# circuito_tesi.net
KiCad netlist of a schematic drawn in EAGLE
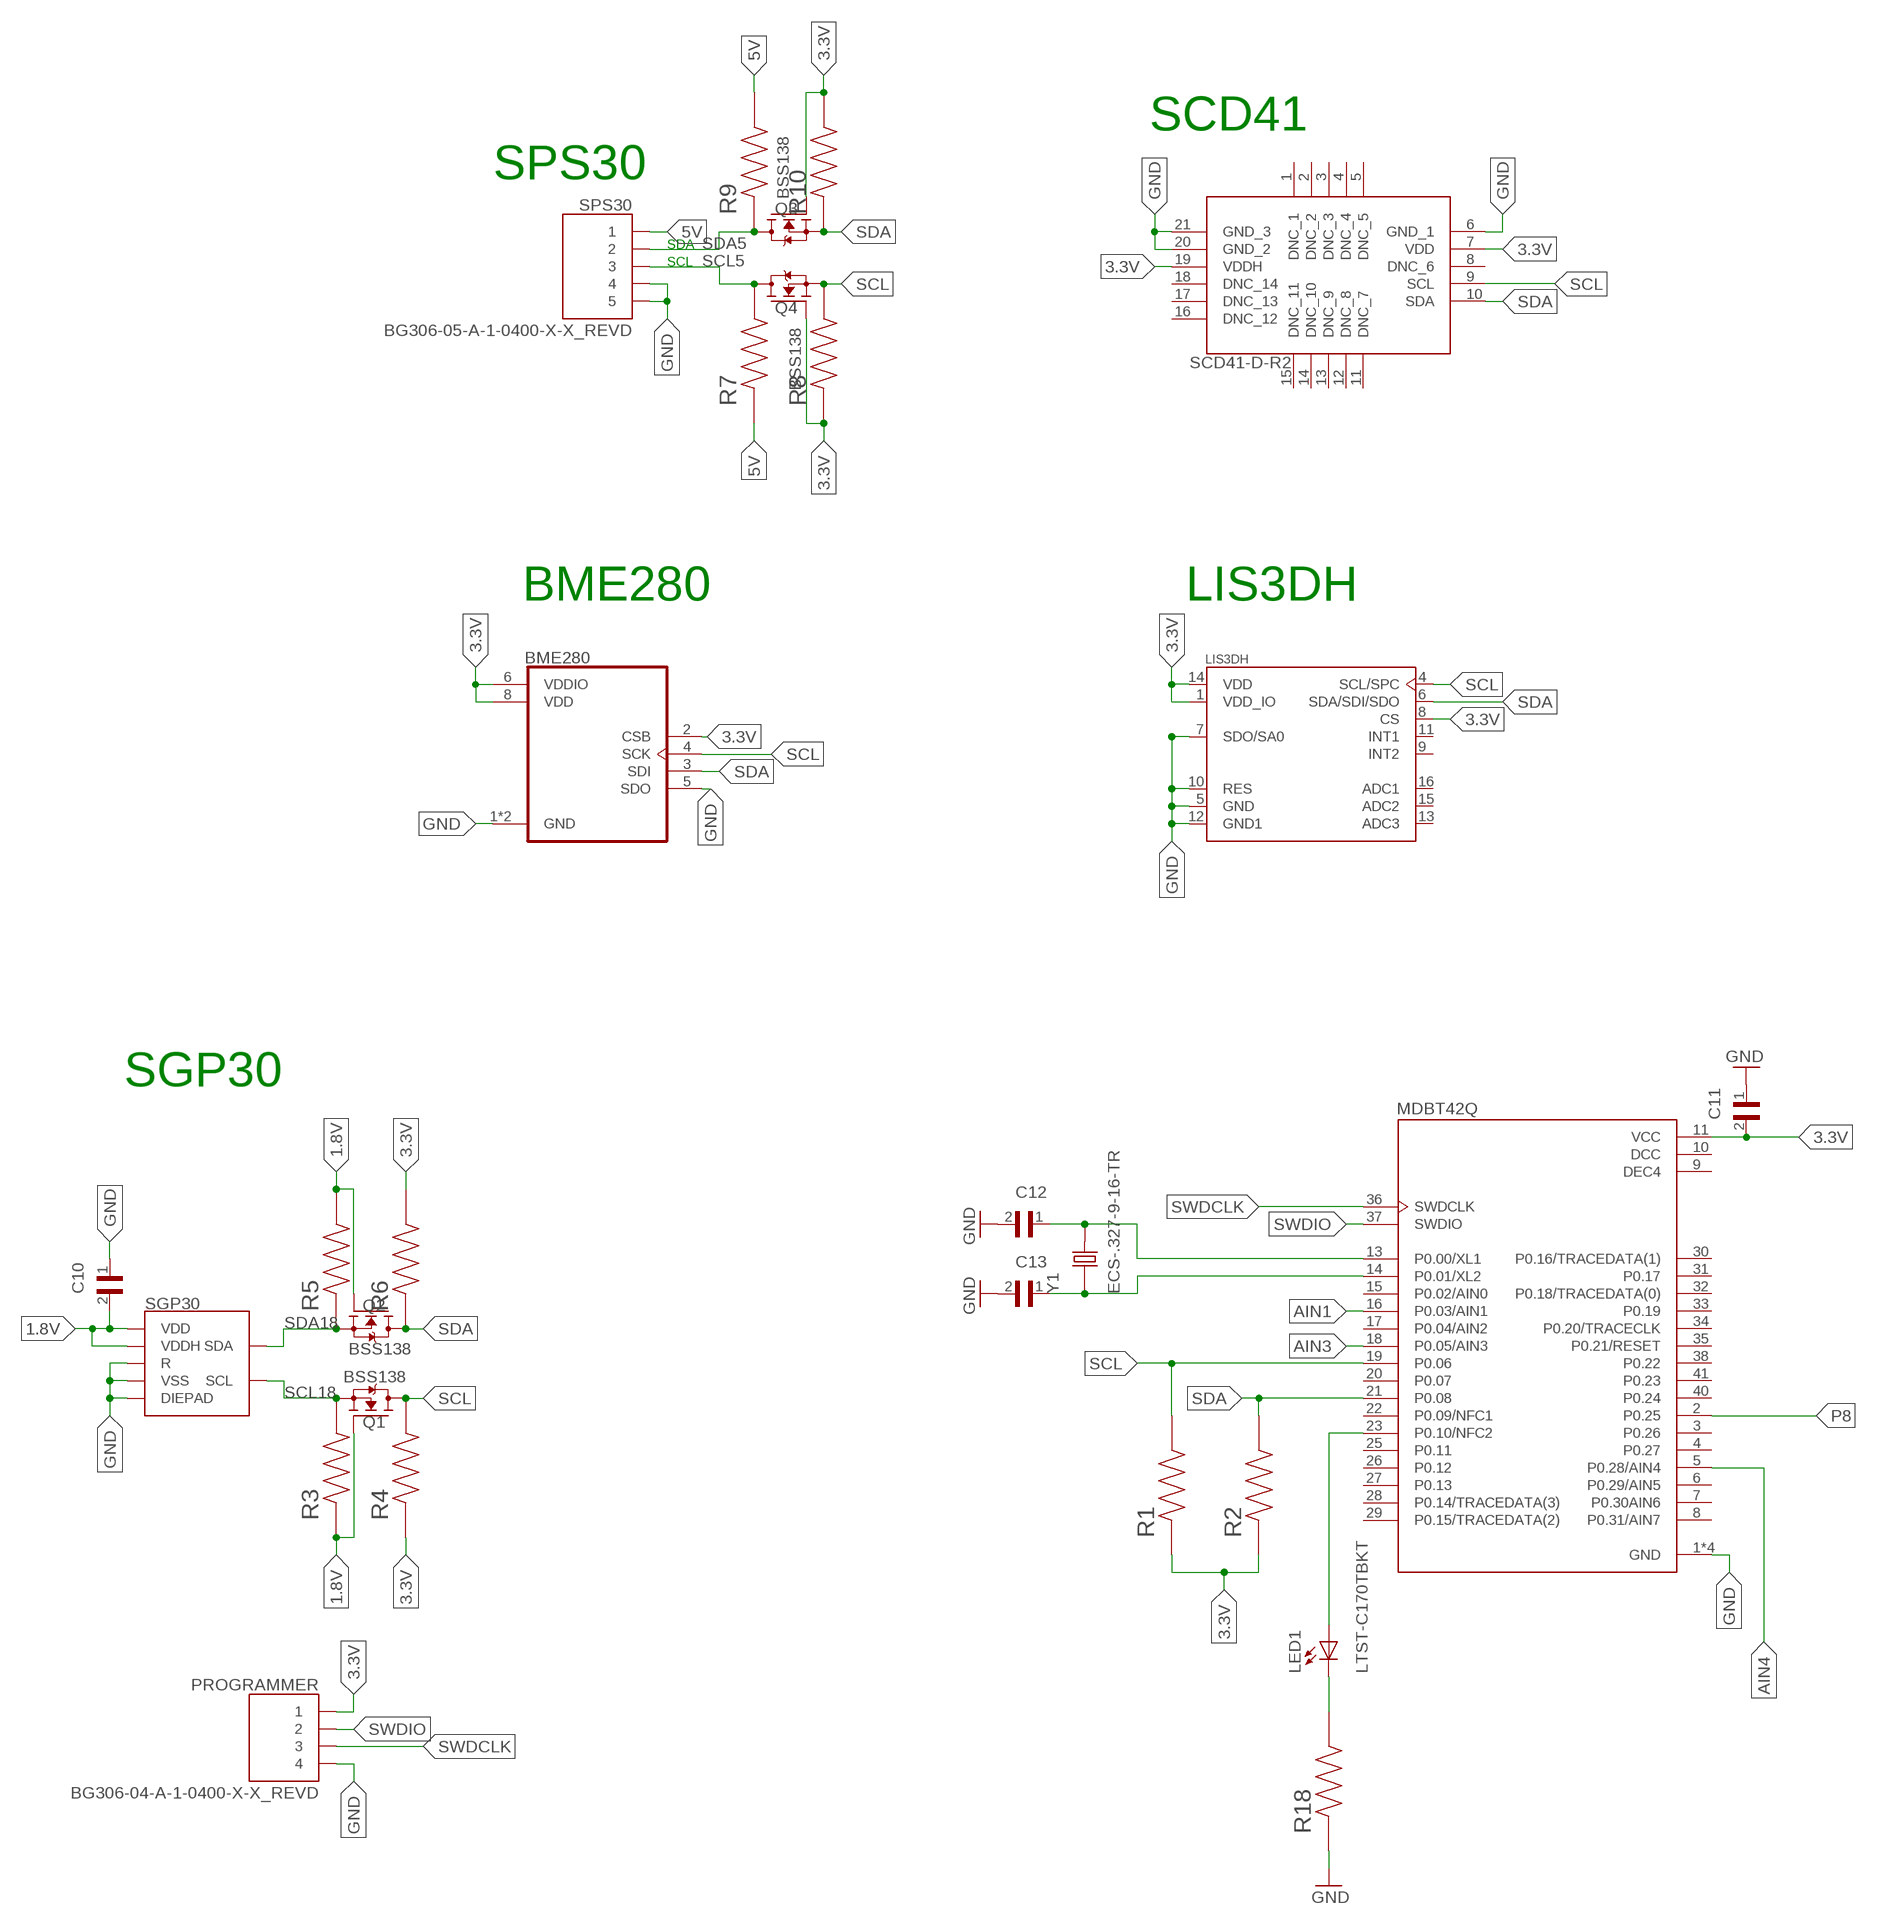
[diagram p0: schematic, sheet 1, part 1 of 2]
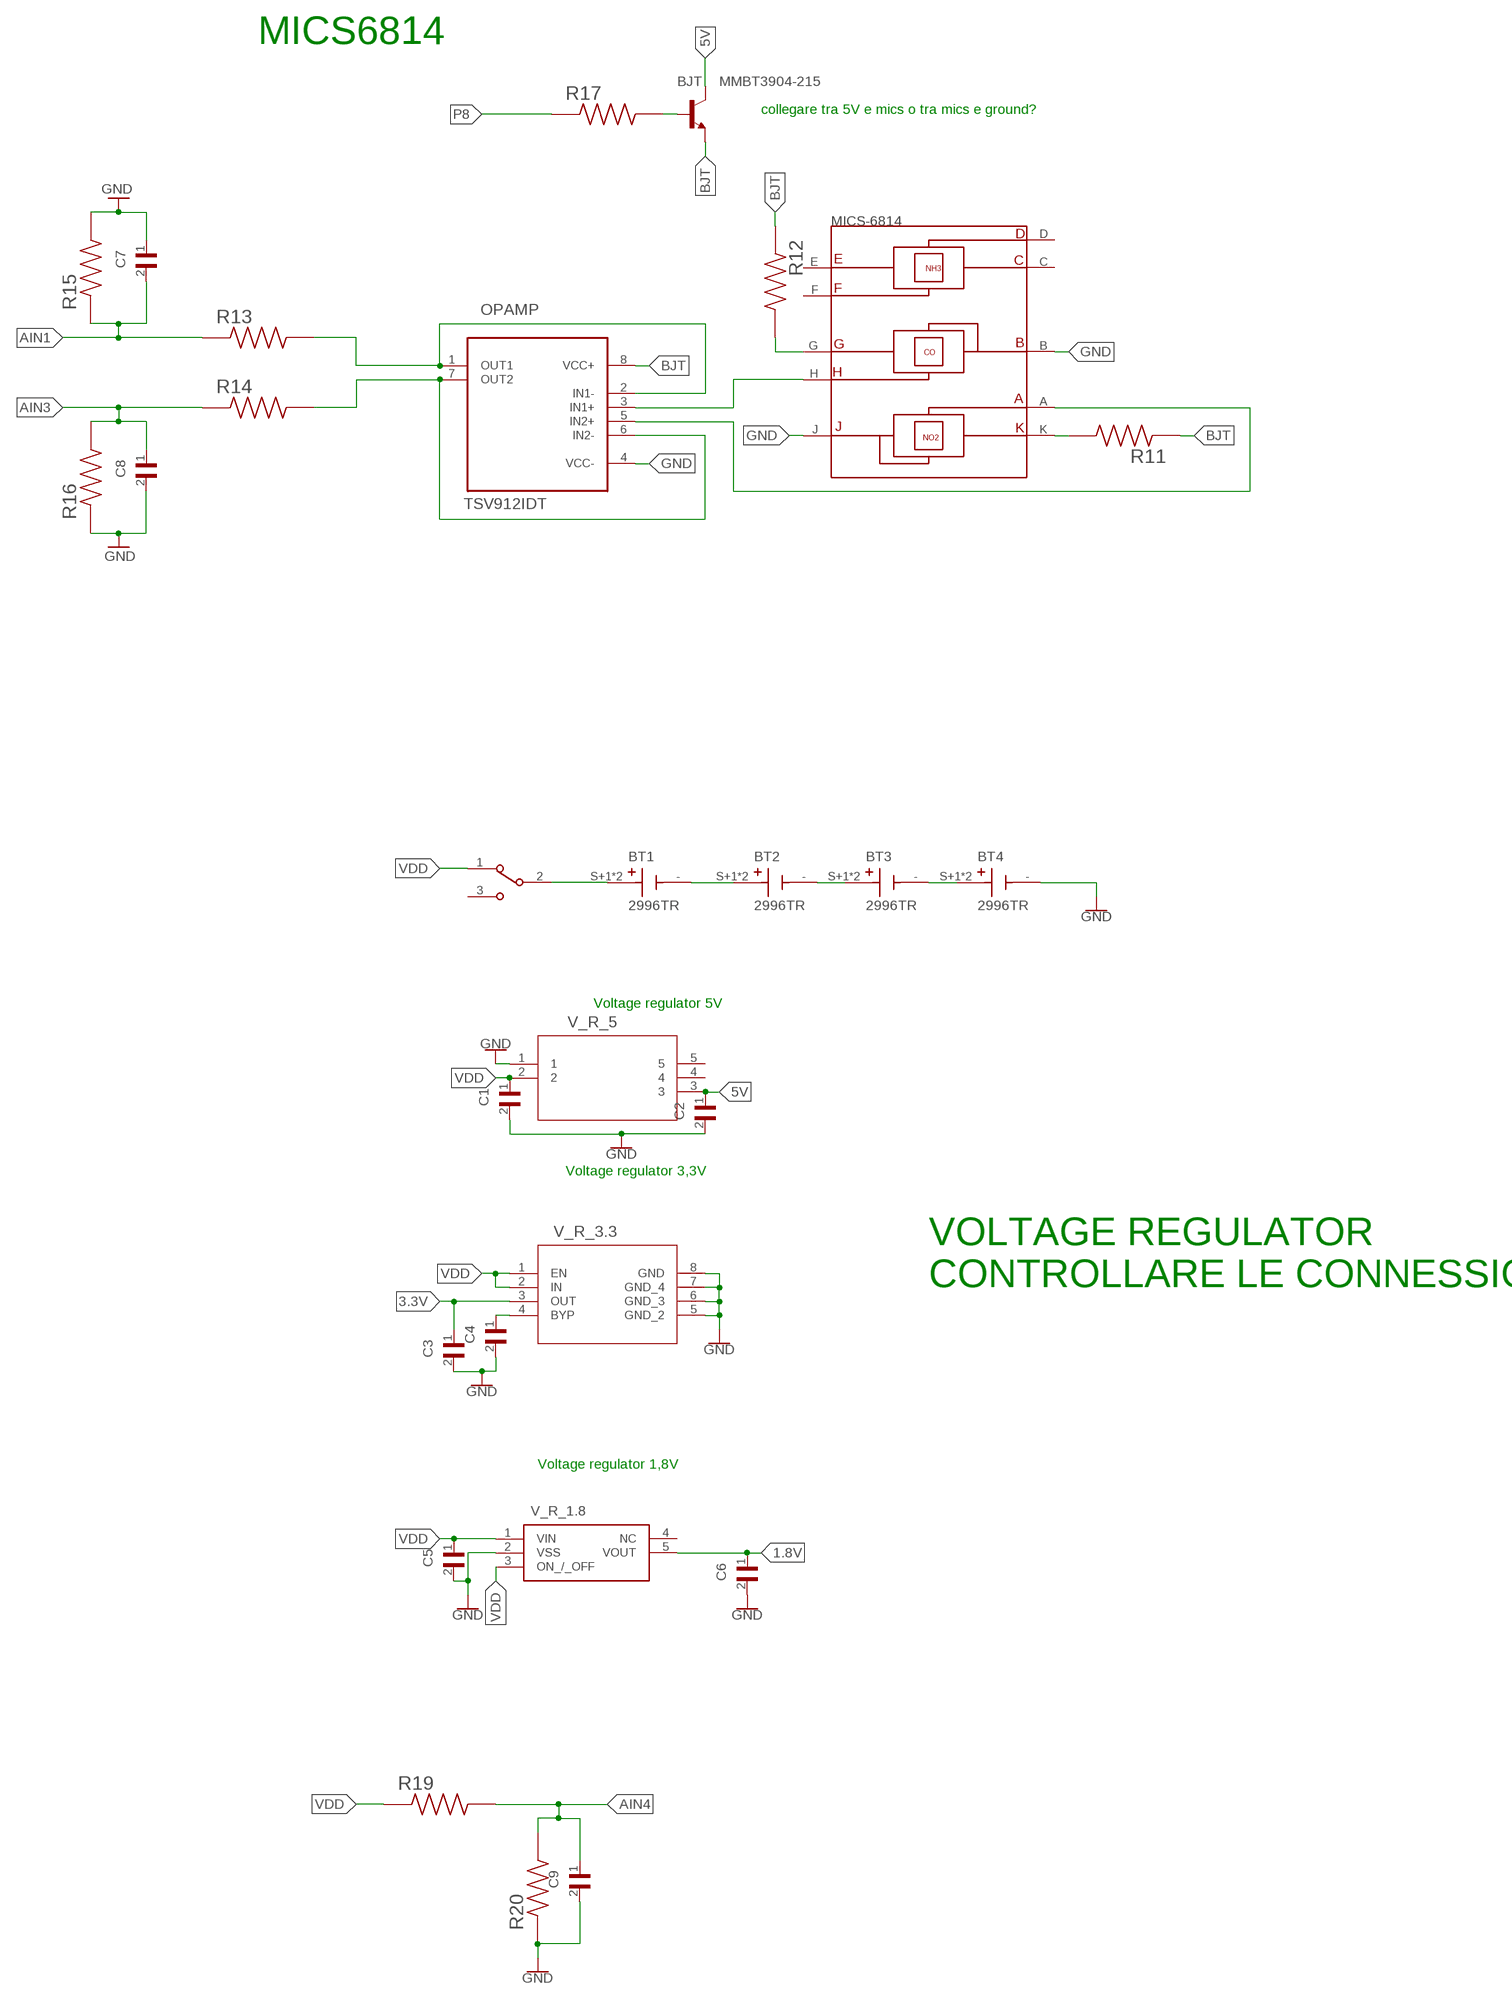
[diagram p1: schematic, sheet 1, part 2 of 2]

(export (version "E")
  (design (tool "Eeschema 10.0.6"))
  (components
    (comp (ref "BJT")
      (value "MMBT3904-215")
      (footprint "eagle-import:SOT95P230X110-3N")
      (fields
        (field (name "DIGI-KEY_PART_NUMBER") "1727-4044-2-ND")
        (field (name "MF") "Nexperia USA")
        (field (name "MP") "MMBT3904,215")
      )
      (libsource (lib "eagle-import") (part "MMBT3904-215"))
    )
    (comp (ref "BT1")
      (value "2996TR")
      (footprint "eagle-import:BAT_2996TR")
      (fields (field (name "DIGI-KEY_PART_NUMBER") "36-2996TR-ND") (field (name "MF") "Keystone Electronics"))
      (libsource (lib "eagle-import") (part "2996TR"))
    )
    (comp (ref "BT2")
      (value "2996TR")
      (footprint "eagle-import:BAT_2996TR")
      (fields (field (name "DIGI-KEY_PART_NUMBER") "36-2996TR-ND") (field (name "MF") "Keystone Electronics"))
      (libsource (lib "eagle-import") (part "2996TR"))
    )
    (comp (ref "BT3")
      (value "2996TR")
      (footprint "eagle-import:BAT_2996TR")
      (fields (field (name "DIGI-KEY_PART_NUMBER") "36-2996TR-ND") (field (name "MF") "Keystone Electronics"))
      (libsource (lib "eagle-import") (part "2996TR"))
    )
    (comp (ref "BT4")
      (value "2996TR")
      (footprint "eagle-import:BAT_2996TR")
      (fields (field (name "DIGI-KEY_PART_NUMBER") "36-2996TR-ND") (field (name "MF") "Keystone Electronics"))
      (libsource (lib "eagle-import") (part "2996TR"))
    )
    (comp (ref "C1")
      (value "C0402H102J5GACTU")
      (footprint "eagle-import:CAPC1005X55N")
      (fields (field (name "MF") "KEMET"))
      (libsource (lib "eagle-import") (part "C0402H102J5GACTU"))
    )
    (comp (ref "C2")
      (value "C0402H102J5GACTU")
      (footprint "eagle-import:CAPC1005X55N")
      (fields (field (name "MF") "KEMET"))
      (libsource (lib "eagle-import") (part "C0402H102J5GACTU"))
    )
    (comp (ref "C3")
      (value "C0402H102J5GACTU")
      (footprint "eagle-import:CAPC1005X55N")
      (fields (field (name "MF") "KEMET"))
      (libsource (lib "eagle-import") (part "C0402H102J5GACTU"))
    )
    (comp (ref "C4")
      (value "C0402H102J5GACTU")
      (footprint "eagle-import:CAPC1005X55N")
      (fields (field (name "MF") "KEMET"))
      (libsource (lib "eagle-import") (part "C0402H102J5GACTU"))
    )
    (comp (ref "C5")
      (value "C0402H102J5GACTU")
      (footprint "eagle-import:CAPC1005X55N")
      (fields (field (name "MF") "KEMET"))
      (libsource (lib "eagle-import") (part "C0402H102J5GACTU"))
    )
    (comp (ref "C6")
      (value "C0402H102J5GACTU")
      (footprint "eagle-import:CAPC1005X55N")
      (fields (field (name "MF") "KEMET"))
      (libsource (lib "eagle-import") (part "C0402H102J5GACTU"))
    )
    (comp (ref "C7")
      (value "C0402H102J5GACTU")
      (footprint "eagle-import:CAPC1005X55N")
      (fields (field (name "MF") "KEMET"))
      (libsource (lib "eagle-import") (part "C0402H102J5GACTU"))
    )
    (comp (ref "C8")
      (value "C0402H102J5GACTU")
      (footprint "eagle-import:CAPC1005X55N")
      (fields (field (name "MF") "KEMET"))
      (libsource (lib "eagle-import") (part "C0402H102J5GACTU"))
    )
    (comp (ref "C9")
      (value "C0402H102J5GACTU")
      (footprint "eagle-import:CAPC1005X55N")
      (fields (field (name "MF") "KEMET"))
      (libsource (lib "eagle-import") (part "C0402H102J5GACTU"))
    )
    (comp (ref "C10")
      (value "C0402H102J5GACTU")
      (footprint "eagle-import:CAPC1005X55N")
      (fields (field (name "MF") "KEMET"))
      (libsource (lib "eagle-import") (part "C0402H102J5GACTU"))
    )
    (comp (ref "C11")
      (value "C0402H102J5GACTU")
      (footprint "eagle-import:CAPC1005X55N")
      (fields (field (name "MF") "KEMET"))
      (libsource (lib "eagle-import") (part "C0402H102J5GACTU"))
    )
    (comp (ref "C12")
      (value "C0402H102J5GACTU")
      (footprint "eagle-import:CAPC1005X55N")
      (fields (field (name "MF") "KEMET"))
      (libsource (lib "eagle-import") (part "C0402H102J5GACTU"))
    )
    (comp (ref "C13")
      (value "C0402H102J5GACTU")
      (footprint "eagle-import:CAPC1005X55N")
      (fields (field (name "MF") "KEMET"))
      (libsource (lib "eagle-import") (part "C0402H102J5GACTU"))
    )
    (comp (ref "IC1")
      (value "SCD41-D-R2")
      (footprint "eagle-import:SCD41DR2")
      (fields (field (name "MOUSER_PART_NUMBER") "403-SCD41-D-R2"))
      (libsource (lib "eagle-import") (part "SCD41-D-R2"))
    )
    (comp (ref "LED1")
      (value "LTST-C170TBKT")
      (footprint "eagle-import:DIOC200X125X110")
      (fields (field (name "MF") "Lite-On Electronics"))
      (libsource (lib "eagle-import") (part "LTST-C170TBKT"))
    )
    (comp (ref "MDBT42Q")
      (value "317030213")
      (footprint "eagle-import:XCVR_317030213")
      (fields (field (name "DIGI-KEY_PART_NUMBER") "1597-1434-ND") (field (name "MF") "Seeed Technology"))
      (libsource (lib "eagle-import") (part "317030213"))
    )
    (comp (ref "OPAMP")
      (value "TSV912IDT")
      (footprint "eagle-import:SOIC127P600X175-8N")
      (fields (field (name "MF") "STMicroelectronics"))
      (libsource (lib "eagle-import") (part "TSV912IDT"))
    )
    (comp (ref "PROGRAMMER")
      (value "BG306-04-A-1-0400-X-X_REVD")
      (footprint "eagle-import:GCT_BG306-04-A-1-0400-X-X_REVD")
      (fields
        (field (name "DIGI-KEY_PART_NUMBER") "2073-BG306-04-A-1-0400-L-BTR-ND")
        (field (name "MF") "Global Connector Technology")
        (field (name "MP") "BG306-04-A-1-0400-L-B")
      )
      (libsource (lib "eagle-import") (part "BG306-04-A-1-0400-X-X_REVD"))
    )
    (comp (ref "Q1")
      (value "BSS138")
      (footprint "eagle-import:SOT95P240X111-3N")
      (fields (field (name "DIGI-KEY_PART_NUMBER") "BSS138TR-ND") (field (name "MF") "ON Semiconductor"))
      (libsource (lib "eagle-import") (part "BSS138"))
    )
    (comp (ref "Q2")
      (value "BSS138")
      (footprint "eagle-import:SOT95P240X111-3N")
      (fields (field (name "DIGI-KEY_PART_NUMBER") "BSS138TR-ND") (field (name "MF") "ON Semiconductor"))
      (libsource (lib "eagle-import") (part "BSS138"))
    )
    (comp (ref "Q3")
      (value "BSS138")
      (footprint "eagle-import:SOT95P240X111-3N")
      (fields (field (name "DIGI-KEY_PART_NUMBER") "BSS138TR-ND") (field (name "MF") "ON Semiconductor"))
      (libsource (lib "eagle-import") (part "BSS138"))
    )
    (comp (ref "Q4")
      (value "BSS138")
      (footprint "eagle-import:SOT95P240X111-3N")
      (fields (field (name "DIGI-KEY_PART_NUMBER") "BSS138TR-ND") (field (name "MF") "ON Semiconductor"))
      (libsource (lib "eagle-import") (part "BSS138"))
    )
    (comp (ref "R1")
      (value "8-1879333-9")
      (footprint "eagle-import:RESC1005X35N")
      (fields (field (name "MF") "TE Connectivity"))
      (libsource (lib "eagle-import") (part "8-1879333-9"))
    )
    (comp (ref "R2")
      (value "8-1879333-9")
      (footprint "eagle-import:RESC1005X35N")
      (fields (field (name "MF") "TE Connectivity"))
      (libsource (lib "eagle-import") (part "8-1879333-9"))
    )
    (comp (ref "R3")
      (value "8-1879333-9")
      (footprint "eagle-import:RESC1005X35N")
      (fields (field (name "MF") "TE Connectivity"))
      (libsource (lib "eagle-import") (part "8-1879333-9"))
    )
    (comp (ref "R4")
      (value "8-1879333-9")
      (footprint "eagle-import:RESC1005X35N")
      (fields (field (name "MF") "TE Connectivity"))
      (libsource (lib "eagle-import") (part "8-1879333-9"))
    )
    (comp (ref "R5")
      (value "8-1879333-9")
      (footprint "eagle-import:RESC1005X35N")
      (fields (field (name "MF") "TE Connectivity"))
      (libsource (lib "eagle-import") (part "8-1879333-9"))
    )
    (comp (ref "R6")
      (value "8-1879333-9")
      (footprint "eagle-import:RESC1005X35N")
      (fields (field (name "MF") "TE Connectivity"))
      (libsource (lib "eagle-import") (part "8-1879333-9"))
    )
    (comp (ref "R7")
      (value "8-1879333-9")
      (footprint "eagle-import:RESC1005X35N")
      (fields (field (name "MF") "TE Connectivity"))
      (libsource (lib "eagle-import") (part "8-1879333-9"))
    )
    (comp (ref "R8")
      (value "8-1879333-9")
      (footprint "eagle-import:RESC1005X35N")
      (fields (field (name "MF") "TE Connectivity"))
      (libsource (lib "eagle-import") (part "8-1879333-9"))
    )
    (comp (ref "R9")
      (value "8-1879333-9")
      (footprint "eagle-import:RESC1005X35N")
      (fields (field (name "MF") "TE Connectivity"))
      (libsource (lib "eagle-import") (part "8-1879333-9"))
    )
    (comp (ref "R10")
      (value "8-1879333-9")
      (footprint "eagle-import:RESC1005X35N")
      (fields (field (name "MF") "TE Connectivity"))
      (libsource (lib "eagle-import") (part "8-1879333-9"))
    )
    (comp (ref "R11")
      (value "8-1879333-9")
      (footprint "eagle-import:RESC1005X35N")
      (fields (field (name "MF") "TE Connectivity"))
      (libsource (lib "eagle-import") (part "8-1879333-9"))
    )
    (comp (ref "R12")
      (value "8-1879333-9")
      (footprint "eagle-import:RESC1005X35N")
      (fields (field (name "MF") "TE Connectivity"))
      (libsource (lib "eagle-import") (part "8-1879333-9"))
    )
    (comp (ref "R13")
      (value "8-1879333-9")
      (footprint "eagle-import:RESC1005X35N")
      (fields (field (name "MF") "TE Connectivity"))
      (libsource (lib "eagle-import") (part "8-1879333-9"))
    )
    (comp (ref "R14")
      (value "8-1879333-9")
      (footprint "eagle-import:RESC1005X35N")
      (fields (field (name "MF") "TE Connectivity"))
      (libsource (lib "eagle-import") (part "8-1879333-9"))
    )
    (comp (ref "R15")
      (value "8-1879333-9")
      (footprint "eagle-import:RESC1005X35N")
      (fields (field (name "MF") "TE Connectivity"))
      (libsource (lib "eagle-import") (part "8-1879333-9"))
    )
    (comp (ref "R16")
      (value "8-1879333-9")
      (footprint "eagle-import:RESC1005X35N")
      (fields (field (name "MF") "TE Connectivity"))
      (libsource (lib "eagle-import") (part "8-1879333-9"))
    )
    (comp (ref "R17")
      (value "8-1879333-9")
      (footprint "eagle-import:RESC1005X35N")
      (fields (field (name "MF") "TE Connectivity"))
      (libsource (lib "eagle-import") (part "8-1879333-9"))
    )
    (comp (ref "R18")
      (value "8-1879333-9")
      (footprint "eagle-import:RESC1005X35N")
      (fields (field (name "MF") "TE Connectivity"))
      (libsource (lib "eagle-import") (part "8-1879333-9"))
    )
    (comp (ref "R19")
      (value "8-1879333-9")
      (footprint "eagle-import:RESC1005X35N")
      (fields (field (name "MF") "TE Connectivity"))
      (libsource (lib "eagle-import") (part "8-1879333-9"))
    )
    (comp (ref "R20")
      (value "8-1879333-9")
      (footprint "eagle-import:RESC1005X35N")
      (fields (field (name "MF") "TE Connectivity"))
      (libsource (lib "eagle-import") (part "8-1879333-9"))
    )
    (comp (ref "S1")
      (value "EG1213")
      (footprint "eagle-import:SW_EG1213")
      (fields (field (name "DIGI-KEY_PART_NUMBER") "EG1906-ND") (field (name "MF") "E-Switch"))
      (libsource (lib "eagle-import") (part "EG1213"))
    )
    (comp (ref "SGP30")
      (value "SGP30")
      (footprint "eagle-import:SGP30")
      (fields (field (name "MF") "Sensirion AG"))
      (libsource (lib "eagle-import") (part "SGP30"))
    )
    (comp (ref "SPS30")
      (value "BG306-05-A-1-0400-X-X_REVD")
      (footprint "eagle-import:GCT_BG306-05-A-1-0400-X-X_REVD")
      (fields
        (field (name "DIGI-KEY_PART_NUMBER") "2073-BG306-05-A-1-0400-L-BTR-ND")
        (field (name "MF") "Global Connector Technology")
        (field (name "MP") "BG306-05-A-1-0400-L-B")
      )
      (libsource (lib "eagle-import") (part "BG306-05-A-1-0400-X-X_REVD"))
    )
    (comp (ref "U3")
      (value "MICS-6814")
      (footprint "eagle-import:SENSOR_MICS-6814")
      (fields (field (name "MF") "MikroElektronika"))
      (libsource (lib "eagle-import") (part "MICS-6814"))
    )
    (comp (ref "U6")
      (value "BME280")
      (footprint "eagle-import:PSON65P250X250X100-8N")
      (fields (field (name "MF") "Bosch"))
      (libsource (lib "eagle-import") (part "BME280"))
    )
    (comp (ref "U7")
      (value "LIS3DH")
      (footprint "eagle-import:PQFN50P300X300X100-16N")
      (fields (field (name "DIGI-KEY_PART_NUMBER") "497-10610-ND") (field (name "MF") "STMicroelectronics"))
      (libsource (lib "eagle-import") (part "LIS3DH"))
    )
    (comp (ref "V_R_1.8")
      (value "S-1318D18-M5T1U4")
      (footprint "eagle-import:SOT95P275X130-5N")
      (fields (field (name "MOUSER_PART_NUMBER") "628-S-1318D18-M5T1U4"))
      (libsource (lib "eagle-import") (part "S-1318D18-M5T1U4"))
    )
    (comp (ref "V_R_3.3")
      (value "MIC5219-3.3YMMMSOP-8LD-PL-1_MCH")
      (footprint "eagle-import:MSOP-8LD-PL-1_MCH")
      (fields
        (field (name "MANUFACTURER_PART_NUMBER") "MIC5219-3.3YMM")
        (field (name "COPYRIGHT") "Copyright (C) 2022 Ultra Librarian. All rights reserved.")
      )
      (libsource (lib "eagle-import") (part "MIC5219-3.3YMMMSOP-8LD-PL-1_MCH"))
    )
    (comp (ref "V_R_5")
      (value "MC78LC50NTRGTSOT23-5_ONS")
      (footprint "eagle-import:TSOT23-5_ONS")
      (fields
        (field (name "MANUFACTURER_PART_NUMBER") "MC78LC50NTRG")
        (field (name "COPYRIGHT") "Copyright (C) 2022 Ultra Librarian. All rights reserved.")
      )
      (libsource (lib "eagle-import") (part "MC78LC50NTRGTSOT23-5_ONS"))
    )
    (comp (ref "Y1")
      (value "ECS-.327-9-16-TR")
      (footprint "eagle-import:XTAL_ECS-.327-9-16-TR")
      (fields (field (name "DIGI-KEY_PART_NUMBER") "XC2132TR-ND") (field (name "MF") "ECS Inc."))
      (libsource (lib "eagle-import") (part "ECS-.327-9-16-TR"))
    )
  )
  (nets
    (net (code "1") (name "/DCC") (class "Default")
      (node (ref "MDBT42Q") (pin "10") (pinfunction "DCC_10") (pintype "power_in"))
    )
    (net (code "2") (name "/DEC4") (class "Default")
      (node (ref "MDBT42Q") (pin "9") (pinfunction "DEC4_9") (pintype "power_in"))
    )
    (net (code "3") (name "/SCL5") (class "Default")
      (node (ref "Q4") (pin "3") (pinfunction "D_3") (pintype "passive"))
      (node (ref "R7") (pin "2") (pinfunction "2_2") (pintype "passive"))
      (node (ref "SPS30") (pin "3") (pinfunction "3_3") (pintype "passive"))
    )
    (net (code "4") (name "/SCL18") (class "Default")
      (node (ref "Q1") (pin "2") (pinfunction "S_2") (pintype "passive"))
      (node (ref "R3") (pin "2") (pinfunction "2_2") (pintype "passive"))
      (node (ref "SGP30") (pin "6") (pinfunction "SCL_6") (pintype "bidirectional"))
    )
    (net (code "5") (name "/SDA5") (class "Default")
      (node (ref "Q3") (pin "3") (pinfunction "D_3") (pintype "passive"))
      (node (ref "R9") (pin "1") (pinfunction "1_1") (pintype "passive"))
      (node (ref "SPS30") (pin "2") (pinfunction "2_2") (pintype "passive"))
    )
    (net (code "6") (name "/SDA18") (class "Default")
      (node (ref "Q2") (pin "2") (pinfunction "S_2") (pintype "passive"))
      (node (ref "R5") (pin "1") (pinfunction "1_1") (pintype "passive"))
      (node (ref "SGP30") (pin "3") (pinfunction "SDA_3") (pintype "bidirectional"))
    )
    (net (code "7") (name "1.8V") (class "Default")
      (node (ref "C10") (pin "2") (pinfunction "2_2") (pintype "passive"))
      (node (ref "C6") (pin "1") (pinfunction "1_1") (pintype "passive"))
      (node (ref "Q1") (pin "1") (pinfunction "G_1") (pintype "passive"))
      (node (ref "Q2") (pin "1") (pinfunction "G_1") (pintype "passive"))
      (node (ref "R3") (pin "1") (pinfunction "1_1") (pintype "passive"))
      (node (ref "R5") (pin "2") (pinfunction "2_2") (pintype "passive"))
      (node (ref "SGP30") (pin "1") (pinfunction "VDD_1") (pintype "bidirectional"))
      (node (ref "SGP30") (pin "5") (pinfunction "VDDH_5") (pintype "bidirectional"))
      (node (ref "V_R_1.8") (pin "5") (pinfunction "VOUT_5") (pintype "bidirectional"))
    )
    (net (code "8") (name "3.3V") (class "Default")
      (node (ref "C11") (pin "2") (pinfunction "2_2") (pintype "passive"))
      (node (ref "C3") (pin "1") (pinfunction "1_1") (pintype "passive"))
      (node (ref "IC1") (pin "19") (pinfunction "VDDH_19") (pintype "bidirectional"))
      (node (ref "IC1") (pin "7") (pinfunction "VDD_7") (pintype "bidirectional"))
      (node (ref "MDBT42Q") (pin "11") (pinfunction "VCC_11") (pintype "power_in"))
      (node (ref "PROGRAMMER") (pin "1") (pinfunction "1_1") (pintype "passive"))
      (node (ref "Q3") (pin "1") (pinfunction "G_1") (pintype "passive"))
      (node (ref "Q4") (pin "1") (pinfunction "G_1") (pintype "passive"))
      (node (ref "R1") (pin "1") (pinfunction "1_1") (pintype "passive"))
      (node (ref "R10") (pin "2") (pinfunction "2_2") (pintype "passive"))
      (node (ref "R2") (pin "1") (pinfunction "1_1") (pintype "passive"))
      (node (ref "R4") (pin "1") (pinfunction "1_1") (pintype "passive"))
      (node (ref "R6") (pin "2") (pinfunction "2_2") (pintype "passive"))
      (node (ref "R8") (pin "1") (pinfunction "1_1") (pintype "passive"))
      (node (ref "U6") (pin "2") (pinfunction "CSB_2") (pintype "input"))
      (node (ref "U6") (pin "6") (pinfunction "VDDIO_6") (pintype "power_in"))
      (node (ref "U6") (pin "8") (pinfunction "VDD_8") (pintype "power_in"))
      (node (ref "U7") (pin "1") (pinfunction "VDD_IO_1") (pintype "power_in"))
      (node (ref "U7") (pin "14") (pinfunction "VDD_14") (pintype "power_in"))
      (node (ref "U7") (pin "8") (pinfunction "CS_8") (pintype "input"))
      (node (ref "V_R_3.3") (pin "3") (pinfunction "OUT_3") (pintype "output"))
    )
    (net (code "9") (name "5V") (class "Default")
      (node (ref "BJT") (pin "3") (pinfunction "C_3") (pintype "passive"))
      (node (ref "C2") (pin "1") (pinfunction "1_1") (pintype "passive"))
      (node (ref "R7") (pin "1") (pinfunction "1_1") (pintype "passive"))
      (node (ref "R9") (pin "2") (pinfunction "2_2") (pintype "passive"))
      (node (ref "SPS30") (pin "1") (pinfunction "1_1") (pintype "passive"))
      (node (ref "V_R_5") (pin "3") (pinfunction "3_3") (pintype "passive"))
    )
    (net (code "10") (name "AIN1") (class "Default")
      (node (ref "C7") (pin "2") (pinfunction "2_2") (pintype "passive"))
      (node (ref "MDBT42Q") (pin "16") (pinfunction "P0.03/AIN1_16") (pintype "bidirectional"))
      (node (ref "R13") (pin "1") (pinfunction "1_1") (pintype "passive"))
      (node (ref "R15") (pin "1") (pinfunction "1_1") (pintype "passive"))
    )
    (net (code "11") (name "AIN3") (class "Default")
      (node (ref "C8") (pin "1") (pinfunction "1_1") (pintype "passive"))
      (node (ref "MDBT42Q") (pin "18") (pinfunction "P0.05/AIN3_18") (pintype "bidirectional"))
      (node (ref "R14") (pin "1") (pinfunction "1_1") (pintype "passive"))
      (node (ref "R16") (pin "2") (pinfunction "2_2") (pintype "passive"))
    )
    (net (code "12") (name "AIN4") (class "Default")
      (node (ref "C9") (pin "1") (pinfunction "1_1") (pintype "passive"))
      (node (ref "MDBT42Q") (pin "5") (pinfunction "P0.28/AIN4_5") (pintype "bidirectional"))
      (node (ref "R19") (pin "2") (pinfunction "2_2") (pintype "passive"))
      (node (ref "R20") (pin "2") (pinfunction "2_2") (pintype "passive"))
    )
    (net (code "13") (name "BJT") (class "Default")
      (node (ref "BJT") (pin "2") (pinfunction "E_2") (pintype "passive"))
      (node (ref "OPAMP") (pin "8") (pinfunction "VCC+_8") (pintype "power_in"))
      (node (ref "R11") (pin "1") (pinfunction "1_1") (pintype "passive"))
      (node (ref "R12") (pin "1") (pinfunction "1_1") (pintype "passive"))
    )
    (net (code "14") (name "GND") (class "Default")
      (node (ref "BT4") (pin "-") (pinfunction "-_-") (pintype "passive"))
      (node (ref "C1") (pin "2") (pinfunction "2_2") (pintype "passive"))
      (node (ref "C10") (pin "1") (pinfunction "1_1") (pintype "passive"))
      (node (ref "C11") (pin "1") (pinfunction "1_1") (pintype "passive"))
      (node (ref "C12") (pin "2") (pinfunction "2_2") (pintype "passive"))
      (node (ref "C13") (pin "2") (pinfunction "2_2") (pintype "passive"))
      (node (ref "C2") (pin "2") (pinfunction "2_2") (pintype "passive"))
      (node (ref "C3") (pin "2") (pinfunction "2_2") (pintype "passive"))
      (node (ref "C4") (pin "2") (pinfunction "2_2") (pintype "passive"))
      (node (ref "C5") (pin "2") (pinfunction "2_2") (pintype "passive"))
      (node (ref "C6") (pin "2") (pinfunction "2_2") (pintype "passive"))
      (node (ref "C7") (pin "1") (pinfunction "1_1") (pintype "passive"))
      (node (ref "C8") (pin "2") (pinfunction "2_2") (pintype "passive"))
      (node (ref "C9") (pin "2") (pinfunction "2_2") (pintype "passive"))
      (node (ref "IC1") (pin "20") (pinfunction "GND_2_20") (pintype "bidirectional"))
      (node (ref "IC1") (pin "21") (pinfunction "GND_3_21") (pintype "bidirectional"))
      (node (ref "IC1") (pin "6") (pinfunction "GND_1_6") (pintype "bidirectional"))
      (node (ref "MDBT42Q") (pin "1") (pinfunction "GND_1") (pintype "power_in"))
      (node (ref "MDBT42Q") (pin "12") (pinfunction "GND_12") (pintype "power_in"))
      (node (ref "MDBT42Q") (pin "24") (pinfunction "GND_24") (pintype "power_in"))
      (node (ref "MDBT42Q") (pin "39") (pinfunction "GND_39") (pintype "power_in"))
      (node (ref "OPAMP") (pin "4") (pinfunction "VCC-_4") (pintype "power_in"))
      (node (ref "PROGRAMMER") (pin "4") (pinfunction "4_4") (pintype "passive"))
      (node (ref "R15") (pin "2") (pinfunction "2_2") (pintype "passive"))
      (node (ref "R16") (pin "1") (pinfunction "1_1") (pintype "passive"))
      (node (ref "R18") (pin "1") (pinfunction "1_1") (pintype "passive"))
      (node (ref "R20") (pin "1") (pinfunction "1_1") (pintype "passive"))
      (node (ref "SGP30") (pin "2") (pinfunction "VSS_2") (pintype "bidirectional"))
      (node (ref "SGP30") (pin "4") (pinfunction "R_4") (pintype "bidirectional"))
      (node (ref "SGP30") (pin "DIEPAD") (pinfunction "DIEPAD_DIEPAD") (pintype "bidirectional"))
      (node (ref "SPS30") (pin "4") (pinfunction "4_4") (pintype "passive"))
      (node (ref "SPS30") (pin "5") (pinfunction "5_5") (pintype "passive"))
      (node (ref "U3") (pin "B") (pinfunction "RH1/RS1_RED_B") (pintype "passive"))
      (node (ref "U3") (pin "J") (pinfunction "RH1/RS1_OX_J") (pintype "passive"))
      (node (ref "U6") (pin "1") (pinfunction "GND_1") (pintype "power_in"))
      (node (ref "U6") (pin "5") (pinfunction "SDO_5") (pintype "bidirectional"))
      (node (ref "U6") (pin "7") (pinfunction "GND_7") (pintype "power_in"))
      (node (ref "U7") (pin "10") (pinfunction "RES_10") (pintype "power_in"))
      (node (ref "U7") (pin "12") (pinfunction "GND1_12") (pintype "power_in"))
      (node (ref "U7") (pin "5") (pinfunction "GND_5") (pintype "power_in"))
      (node (ref "U7") (pin "7") (pinfunction "SDO/SA0_7") (pintype "output"))
      (node (ref "V_R_1.8") (pin "2") (pinfunction "VSS_2") (pintype "bidirectional"))
      (node (ref "V_R_3.3") (pin "5") (pinfunction "GND_2_5") (pintype "passive"))
      (node (ref "V_R_3.3") (pin "6") (pinfunction "GND_3_6") (pintype "passive"))
      (node (ref "V_R_3.3") (pin "7") (pinfunction "GND_4_7") (pintype "passive"))
      (node (ref "V_R_3.3") (pin "8") (pinfunction "GND_8") (pintype "passive"))
      (node (ref "V_R_5") (pin "1") (pinfunction "1_1") (pintype "passive"))
    )
    (net (code "15") (name "Net-(BJT-B)") (class "Default")
      (node (ref "BJT") (pin "1") (pinfunction "B_1") (pintype "passive"))
      (node (ref "R17") (pin "2") (pinfunction "2_2") (pintype "passive"))
    )
    (net (code "16") (name "Net-(BT1-+-PadS+1)") (class "Default")
      (node (ref "BT1") (pin "S+1") (pinfunction "+_S+1") (pintype "passive"))
      (node (ref "BT1") (pin "S+2") (pinfunction "+_S+2") (pintype "passive"))
      (node (ref "S1") (pin "2") (pinfunction "2_2") (pintype "passive"))
    )
    (net (code "17") (name "Net-(BT1-Pad-)") (class "Default")
      (node (ref "BT1") (pin "-") (pinfunction "-_-") (pintype "passive"))
      (node (ref "BT2") (pin "S+1") (pinfunction "+_S+1") (pintype "passive"))
      (node (ref "BT2") (pin "S+2") (pinfunction "+_S+2") (pintype "passive"))
    )
    (net (code "18") (name "Net-(BT2-Pad-)") (class "Default")
      (node (ref "BT2") (pin "-") (pinfunction "-_-") (pintype "passive"))
      (node (ref "BT3") (pin "S+1") (pinfunction "+_S+1") (pintype "passive"))
      (node (ref "BT3") (pin "S+2") (pinfunction "+_S+2") (pintype "passive"))
    )
    (net (code "19") (name "Net-(BT3-Pad-)") (class "Default")
      (node (ref "BT3") (pin "-") (pinfunction "-_-") (pintype "passive"))
      (node (ref "BT4") (pin "S+1") (pinfunction "+_S+1") (pintype "passive"))
      (node (ref "BT4") (pin "S+2") (pinfunction "+_S+2") (pintype "passive"))
    )
    (net (code "20") (name "Net-(LED1-Pad-)") (class "Default")
      (node (ref "LED1") (pin "-") (pinfunction "-_-") (pintype "passive"))
      (node (ref "R18") (pin "2") (pinfunction "2_2") (pintype "passive"))
    )
    (net (code "21") (name "Net-(MDBT42Q-P0.00{slash}XL1)") (class "Default")
      (node (ref "C12") (pin "1") (pinfunction "1_1") (pintype "passive"))
      (node (ref "MDBT42Q") (pin "13") (pinfunction "P0.00/XL1_13") (pintype "bidirectional"))
      (node (ref "Y1") (pin "2") (pinfunction "2_2") (pintype "passive"))
    )
    (net (code "22") (name "Net-(MDBT42Q-P0.01{slash}XL2)") (class "Default")
      (node (ref "C13") (pin "1") (pinfunction "1_1") (pintype "passive"))
      (node (ref "MDBT42Q") (pin "14") (pinfunction "P0.01/XL2_14") (pintype "bidirectional"))
      (node (ref "Y1") (pin "1") (pinfunction "1_1") (pintype "passive"))
    )
    (net (code "23") (name "Net-(MDBT42Q-P0.10{slash}NFC2)") (class "Default")
      (node (ref "LED1") (pin "+") (pinfunction "+_+") (pintype "passive"))
      (node (ref "MDBT42Q") (pin "23") (pinfunction "P0.10/NFC2_23") (pintype "bidirectional"))
    )
    (net (code "24") (name "Net-(OPAMP-IN1+)") (class "Default")
      (node (ref "OPAMP") (pin "3") (pinfunction "IN1+_3") (pintype "input"))
      (node (ref "U3") (pin "H") (pinfunction "RS2_RED_H") (pintype "passive"))
    )
    (net (code "25") (name "Net-(OPAMP-IN1-)") (class "Default")
      (node (ref "OPAMP") (pin "1") (pinfunction "OUT1_1") (pintype "output"))
      (node (ref "OPAMP") (pin "2") (pinfunction "IN1-_2") (pintype "input"))
      (node (ref "R13") (pin "2") (pinfunction "2_2") (pintype "passive"))
    )
    (net (code "26") (name "Net-(OPAMP-IN2+)") (class "Default")
      (node (ref "OPAMP") (pin "5") (pinfunction "IN2+_5") (pintype "input"))
      (node (ref "U3") (pin "A") (pinfunction "RS2_A") (pintype "passive"))
    )
    (net (code "27") (name "Net-(OPAMP-IN2-)") (class "Default")
      (node (ref "OPAMP") (pin "6") (pinfunction "IN2-_6") (pintype "input"))
      (node (ref "OPAMP") (pin "7") (pinfunction "OUT2_7") (pintype "output"))
      (node (ref "R14") (pin "2") (pinfunction "2_2") (pintype "passive"))
    )
    (net (code "28") (name "Net-(U3-RH2_OX)") (class "Default")
      (node (ref "R11") (pin "2") (pinfunction "2_2") (pintype "passive"))
      (node (ref "U3") (pin "K") (pinfunction "RH2_OX_K") (pintype "passive"))
    )
    (net (code "29") (name "Net-(U3-RH2_RED)") (class "Default")
      (node (ref "R12") (pin "2") (pinfunction "2_2") (pintype "passive"))
      (node (ref "U3") (pin "G") (pinfunction "RH2_RED_G") (pintype "passive"))
    )
    (net (code "30") (name "Net-(V_R_3.3-BYP)") (class "Default")
      (node (ref "C4") (pin "1") (pinfunction "1_1") (pintype "passive"))
      (node (ref "V_R_3.3") (pin "4") (pinfunction "BYP_4") (pintype "passive"))
    )
    (net (code "31") (name "P8") (class "Default")
      (node (ref "MDBT42Q") (pin "2") (pinfunction "P0.25_2") (pintype "bidirectional"))
      (node (ref "R17") (pin "1") (pinfunction "1_1") (pintype "passive"))
    )
    (net (code "32") (name "SCL") (class "Default")
      (node (ref "IC1") (pin "9") (pinfunction "SCL_9") (pintype "bidirectional"))
      (node (ref "MDBT42Q") (pin "19") (pinfunction "P0.06_19") (pintype "bidirectional"))
      (node (ref "Q1") (pin "3") (pinfunction "D_3") (pintype "passive"))
      (node (ref "Q4") (pin "2") (pinfunction "S_2") (pintype "passive"))
      (node (ref "R1") (pin "2") (pinfunction "2_2") (pintype "passive"))
      (node (ref "R4") (pin "2") (pinfunction "2_2") (pintype "passive"))
      (node (ref "R8") (pin "2") (pinfunction "2_2") (pintype "passive"))
      (node (ref "U6") (pin "4") (pinfunction "SCK_4") (pintype "input"))
      (node (ref "U7") (pin "4") (pinfunction "SCL/SPC_4") (pintype "input"))
    )
    (net (code "33") (name "SDA") (class "Default")
      (node (ref "IC1") (pin "10") (pinfunction "SDA_10") (pintype "bidirectional"))
      (node (ref "MDBT42Q") (pin "21") (pinfunction "P0.08_21") (pintype "bidirectional"))
      (node (ref "Q2") (pin "3") (pinfunction "D_3") (pintype "passive"))
      (node (ref "Q3") (pin "2") (pinfunction "S_2") (pintype "passive"))
      (node (ref "R10") (pin "1") (pinfunction "1_1") (pintype "passive"))
      (node (ref "R2") (pin "2") (pinfunction "2_2") (pintype "passive"))
      (node (ref "R6") (pin "1") (pinfunction "1_1") (pintype "passive"))
      (node (ref "U6") (pin "3") (pinfunction "SDI_3") (pintype "bidirectional"))
      (node (ref "U7") (pin "6") (pinfunction "SDA/SDI/SDO_6") (pintype "input"))
    )
    (net (code "34") (name "SWDCLK") (class "Default")
      (node (ref "MDBT42Q") (pin "36") (pinfunction "SWDCLK_36") (pintype "input"))
      (node (ref "PROGRAMMER") (pin "3") (pinfunction "3_3") (pintype "passive"))
    )
    (net (code "35") (name "SWDIO") (class "Default")
      (node (ref "MDBT42Q") (pin "37") (pinfunction "SWDIO_37") (pintype "bidirectional"))
      (node (ref "PROGRAMMER") (pin "2") (pinfunction "2_2") (pintype "passive"))
    )
    (net (code "36") (name "VDD") (class "Default")
      (node (ref "C1") (pin "1") (pinfunction "1_1") (pintype "passive"))
      (node (ref "C5") (pin "1") (pinfunction "1_1") (pintype "passive"))
      (node (ref "R19") (pin "1") (pinfunction "1_1") (pintype "passive"))
      (node (ref "S1") (pin "1") (pinfunction "1_1") (pintype "passive"))
      (node (ref "V_R_1.8") (pin "1") (pinfunction "VIN_1") (pintype "bidirectional"))
      (node (ref "V_R_1.8") (pin "3") (pinfunction "ON_/_OFF_3") (pintype "bidirectional"))
      (node (ref "V_R_3.3") (pin "1") (pinfunction "EN_1") (pintype "input"))
      (node (ref "V_R_3.3") (pin "2") (pinfunction "IN_2") (pintype "power_in"))
      (node (ref "V_R_5") (pin "2") (pinfunction "2_2") (pintype "passive"))
    )
    (net (code "37") (name "unconnected-(IC1-DNC_1-Pad1)") (class "Default")
      (node (ref "IC1") (pin "1") (pinfunction "DNC_1_1") (pintype "bidirectional"))
    )
    (net (code "38") (name "unconnected-(IC1-DNC_2-Pad2)") (class "Default")
      (node (ref "IC1") (pin "2") (pinfunction "DNC_2_2") (pintype "bidirectional"))
    )
    (net (code "39") (name "unconnected-(IC1-DNC_3-Pad3)") (class "Default")
      (node (ref "IC1") (pin "3") (pinfunction "DNC_3_3") (pintype "bidirectional"))
    )
    (net (code "40") (name "unconnected-(IC1-DNC_4-Pad4)") (class "Default")
      (node (ref "IC1") (pin "4") (pinfunction "DNC_4_4") (pintype "bidirectional"))
    )
    (net (code "41") (name "unconnected-(IC1-DNC_5-Pad5)") (class "Default")
      (node (ref "IC1") (pin "5") (pinfunction "DNC_5_5") (pintype "bidirectional"))
    )
    (net (code "42") (name "unconnected-(IC1-DNC_6-Pad8)") (class "Default")
      (node (ref "IC1") (pin "8") (pinfunction "DNC_6_8") (pintype "bidirectional"))
    )
    (net (code "43") (name "unconnected-(IC1-DNC_7-Pad11)") (class "Default")
      (node (ref "IC1") (pin "11") (pinfunction "DNC_7_11") (pintype "bidirectional"))
    )
    (net (code "44") (name "unconnected-(IC1-DNC_8-Pad12)") (class "Default")
      (node (ref "IC1") (pin "12") (pinfunction "DNC_8_12") (pintype "bidirectional"))
    )
    (net (code "45") (name "unconnected-(IC1-DNC_9-Pad13)") (class "Default")
      (node (ref "IC1") (pin "13") (pinfunction "DNC_9_13") (pintype "bidirectional"))
    )
    (net (code "46") (name "unconnected-(IC1-DNC_10-Pad14)") (class "Default")
      (node (ref "IC1") (pin "14") (pinfunction "DNC_10_14") (pintype "bidirectional"))
    )
    (net (code "47") (name "unconnected-(IC1-DNC_11-Pad15)") (class "Default")
      (node (ref "IC1") (pin "15") (pinfunction "DNC_11_15") (pintype "bidirectional"))
    )
    (net (code "48") (name "unconnected-(IC1-DNC_12-Pad16)") (class "Default")
      (node (ref "IC1") (pin "16") (pinfunction "DNC_12_16") (pintype "bidirectional"))
    )
    (net (code "49") (name "unconnected-(IC1-DNC_13-Pad17)") (class "Default")
      (node (ref "IC1") (pin "17") (pinfunction "DNC_13_17") (pintype "bidirectional"))
    )
    (net (code "50") (name "unconnected-(IC1-DNC_14-Pad18)") (class "Default")
      (node (ref "IC1") (pin "18") (pinfunction "DNC_14_18") (pintype "bidirectional"))
    )
    (net (code "51") (name "unconnected-(MDBT42Q-P0.02{slash}AIN0-Pad15)") (class "Default")
      (node (ref "MDBT42Q") (pin "15") (pinfunction "P0.02/AIN0_15") (pintype "bidirectional"))
    )
    (net (code "52") (name "unconnected-(MDBT42Q-P0.04{slash}AIN2-Pad17)") (class "Default")
      (node (ref "MDBT42Q") (pin "17") (pinfunction "P0.04/AIN2_17") (pintype "bidirectional"))
    )
    (net (code "53") (name "unconnected-(MDBT42Q-P0.07-Pad20)") (class "Default")
      (node (ref "MDBT42Q") (pin "20") (pinfunction "P0.07_20") (pintype "bidirectional"))
    )
    (net (code "54") (name "unconnected-(MDBT42Q-P0.09{slash}NFC1-Pad22)") (class "Default")
      (node (ref "MDBT42Q") (pin "22") (pinfunction "P0.09/NFC1_22") (pintype "bidirectional"))
    )
    (net (code "55") (name "unconnected-(MDBT42Q-P0.11-Pad25)") (class "Default")
      (node (ref "MDBT42Q") (pin "25") (pinfunction "P0.11_25") (pintype "bidirectional"))
    )
    (net (code "56") (name "unconnected-(MDBT42Q-P0.12-Pad26)") (class "Default")
      (node (ref "MDBT42Q") (pin "26") (pinfunction "P0.12_26") (pintype "bidirectional"))
    )
    (net (code "57") (name "unconnected-(MDBT42Q-P0.13-Pad27)") (class "Default")
      (node (ref "MDBT42Q") (pin "27") (pinfunction "P0.13_27") (pintype "bidirectional"))
    )
    (net (code "58") (name "unconnected-(MDBT42Q-P0.14{slash}TRACEDATA(3)-Pad28)") (class "Default")
      (node (ref "MDBT42Q") (pin "28") (pinfunction "P0.14/TRACEDATA(3)_28") (pintype "bidirectional"))
    )
    (net (code "59") (name "unconnected-(MDBT42Q-P0.15{slash}TRACEDATA(2)-Pad29)") (class "Default")
      (node (ref "MDBT42Q") (pin "29") (pinfunction "P0.15/TRACEDATA(2)_29") (pintype "bidirectional"))
    )
    (net (code "60") (name "unconnected-(MDBT42Q-P0.16{slash}TRACEDATA(1)-Pad30)") (class "Default")
      (node (ref "MDBT42Q") (pin "30") (pinfunction "P0.16/TRACEDATA(1)_30") (pintype "bidirectional"))
    )
    (net (code "61") (name "unconnected-(MDBT42Q-P0.17-Pad31)") (class "Default")
      (node (ref "MDBT42Q") (pin "31") (pinfunction "P0.17_31") (pintype "bidirectional"))
    )
    (net (code "62") (name "unconnected-(MDBT42Q-P0.18{slash}TRACEDATA(0)-Pad32)") (class "Default")
      (node (ref "MDBT42Q") (pin "32") (pinfunction "P0.18/TRACEDATA(0)_32") (pintype "bidirectional"))
    )
    (net (code "63") (name "unconnected-(MDBT42Q-P0.19-Pad33)") (class "Default")
      (node (ref "MDBT42Q") (pin "33") (pinfunction "P0.19_33") (pintype "bidirectional"))
    )
    (net (code "64") (name "unconnected-(MDBT42Q-P0.20{slash}TRACECLK-Pad34)") (class "Default")
      (node (ref "MDBT42Q") (pin "34") (pinfunction "P0.20/TRACECLK_34") (pintype "bidirectional"))
    )
    (net (code "65") (name "unconnected-(MDBT42Q-P0.21{slash}RESET-Pad35)") (class "Default")
      (node (ref "MDBT42Q") (pin "35") (pinfunction "P0.21/RESET_35") (pintype "bidirectional"))
    )
    (net (code "66") (name "unconnected-(MDBT42Q-P0.22-Pad38)") (class "Default")
      (node (ref "MDBT42Q") (pin "38") (pinfunction "P0.22_38") (pintype "bidirectional"))
    )
    (net (code "67") (name "unconnected-(MDBT42Q-P0.23-Pad41)") (class "Default")
      (node (ref "MDBT42Q") (pin "41") (pinfunction "P0.23_41") (pintype "bidirectional"))
    )
    (net (code "68") (name "unconnected-(MDBT42Q-P0.24-Pad40)") (class "Default")
      (node (ref "MDBT42Q") (pin "40") (pinfunction "P0.24_40") (pintype "bidirectional"))
    )
    (net (code "69") (name "unconnected-(MDBT42Q-P0.26-Pad3)") (class "Default")
      (node (ref "MDBT42Q") (pin "3") (pinfunction "P0.26_3") (pintype "bidirectional"))
    )
    (net (code "70") (name "unconnected-(MDBT42Q-P0.27-Pad4)") (class "Default")
      (node (ref "MDBT42Q") (pin "4") (pinfunction "P0.27_4") (pintype "bidirectional"))
    )
    (net (code "71") (name "unconnected-(MDBT42Q-P0.29{slash}AIN5-Pad6)") (class "Default")
      (node (ref "MDBT42Q") (pin "6") (pinfunction "P0.29/AIN5_6") (pintype "bidirectional"))
    )
    (net (code "72") (name "unconnected-(MDBT42Q-P0.30AIN6-Pad7)") (class "Default")
      (node (ref "MDBT42Q") (pin "7") (pinfunction "P0.30AIN6_7") (pintype "bidirectional"))
    )
    (net (code "73") (name "unconnected-(MDBT42Q-P0.31{slash}AIN7-Pad8)") (class "Default")
      (node (ref "MDBT42Q") (pin "8") (pinfunction "P0.31/AIN7_8") (pintype "bidirectional"))
    )
    (net (code "74") (name "unconnected-(S1-Pad3)") (class "Default")
      (node (ref "S1") (pin "3") (pinfunction "3_3") (pintype "passive"))
    )
    (net (code "75") (name "unconnected-(U3-RH1_NH3-PadC)") (class "Default")
      (node (ref "U3") (pin "C") (pinfunction "RH1_NH3_C") (pintype "passive"))
    )
    (net (code "76") (name "unconnected-(U3-RH2_NH3-PadE)") (class "Default")
      (node (ref "U3") (pin "E") (pinfunction "RH2_NH3_E") (pintype "passive"))
    )
    (net (code "77") (name "unconnected-(U3-RS1_NH3-PadD)") (class "Default")
      (node (ref "U3") (pin "D") (pinfunction "RS1_NH3_D") (pintype "passive"))
    )
    (net (code "78") (name "unconnected-(U3-RS2_NH3-PadF)") (class "Default")
      (node (ref "U3") (pin "F") (pinfunction "RS2_NH3_F") (pintype "passive"))
    )
    (net (code "79") (name "unconnected-(U7-ADC1-Pad16)") (class "Default")
      (node (ref "U7") (pin "16") (pinfunction "ADC1_16") (pintype "input"))
    )
    (net (code "80") (name "unconnected-(U7-ADC2-Pad15)") (class "Default")
      (node (ref "U7") (pin "15") (pinfunction "ADC2_15") (pintype "input"))
    )
    (net (code "81") (name "unconnected-(U7-ADC3-Pad13)") (class "Default")
      (node (ref "U7") (pin "13") (pinfunction "ADC3_13") (pintype "input"))
    )
    (net (code "82") (name "unconnected-(U7-INT1-Pad11)") (class "Default")
      (node (ref "U7") (pin "11") (pinfunction "INT1_11") (pintype "input"))
    )
    (net (code "83") (name "unconnected-(U7-INT2-Pad9)") (class "Default")
      (node (ref "U7") (pin "9") (pinfunction "INT2_9") (pintype "input"))
    )
    (net (code "84") (name "unconnected-(V_R_1.8-NC-Pad4)") (class "Default")
      (node (ref "V_R_1.8") (pin "4") (pinfunction "NC_4") (pintype "no_connect"))
    )
    (net (code "85") (name "unconnected-(V_R_5-Pad4)") (class "Default")
      (node (ref "V_R_5") (pin "4") (pinfunction "4_4") (pintype "passive"))
    )
    (net (code "86") (name "unconnected-(V_R_5-Pad5)") (class "Default")
      (node (ref "V_R_5") (pin "5") (pinfunction "5_5") (pintype "passive"))
    )
  )
)
